# Step-sch.net
KiCad netlist of a schematic drawn in EAGLE
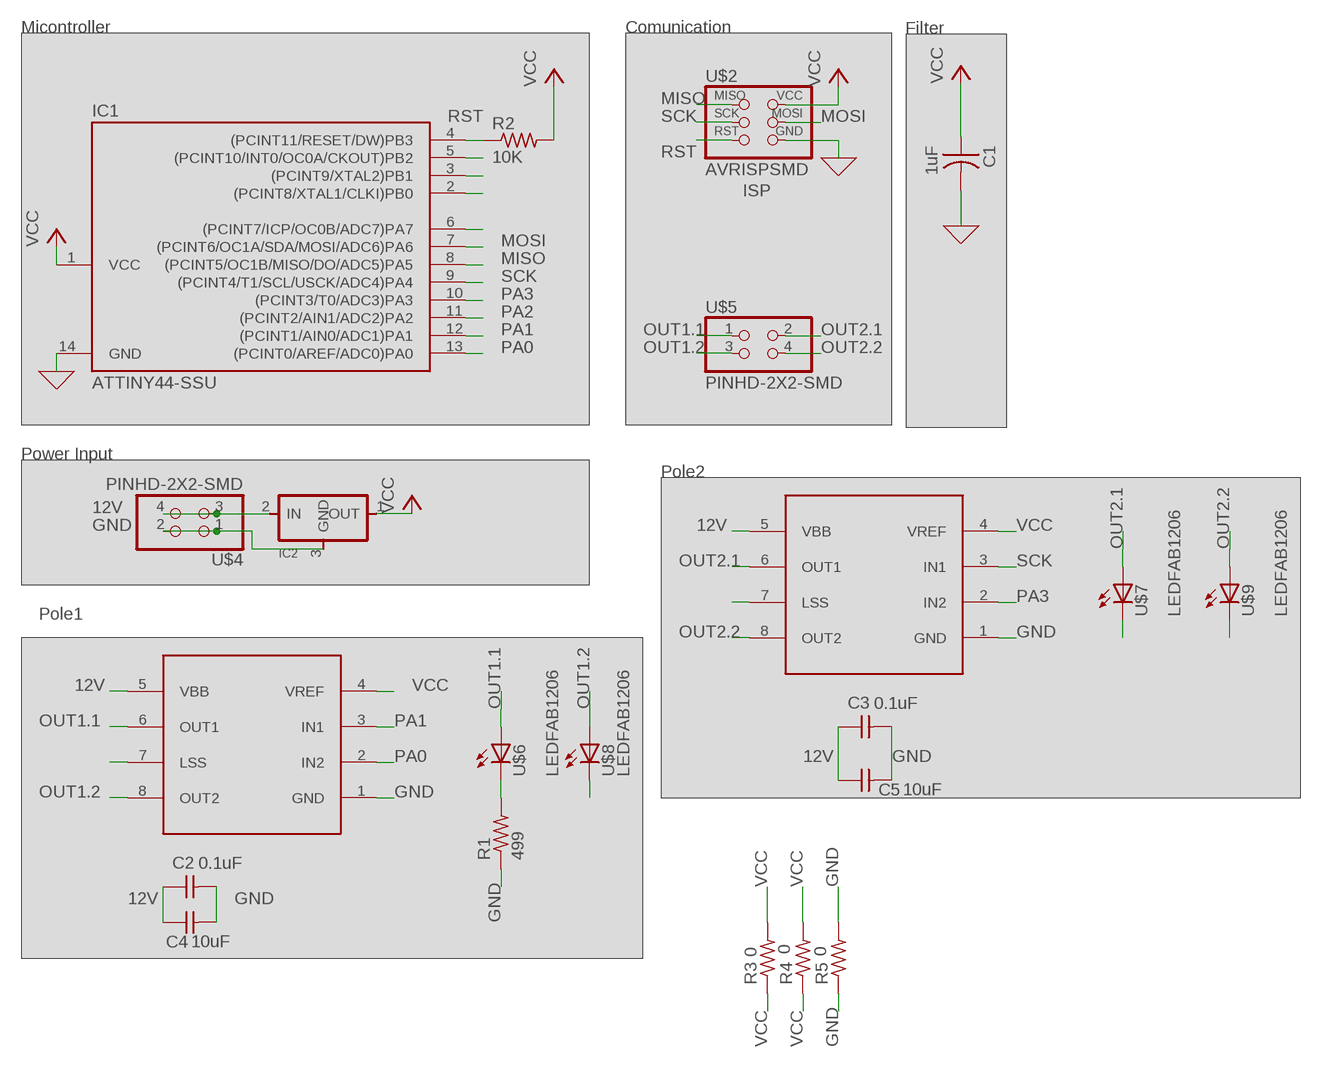
[diagram p0: schematic, sheet 1]

(export (version "E")
  (design (tool "Eeschema 10.0.6"))
  (components
    (comp (ref "C1")
      (value "1uF")
      (footprint "eagle-import:C1206FAB")
      (libsource (lib "eagle-import") (part "CAP-US1206FAB"))
    )
    (comp (ref "C2")
      (value "0.1uF")
      (footprint "eagle-import:C1206FAB")
      (libsource (lib "eagle-import") (part "CAP-UNPOLARIZEDFAB"))
    )
    (comp (ref "C3")
      (value "0.1uF")
      (footprint "eagle-import:C1206FAB")
      (libsource (lib "eagle-import") (part "CAP-UNPOLARIZEDFAB"))
    )
    (comp (ref "C4")
      (value "10uF")
      (footprint "eagle-import:C1206FAB")
      (libsource (lib "eagle-import") (part "CAP-UNPOLARIZEDFAB"))
    )
    (comp (ref "C5")
      (value "10uF")
      (footprint "eagle-import:C1206FAB")
      (libsource (lib "eagle-import") (part "CAP-UNPOLARIZEDFAB"))
    )
    (comp (ref "IC1")
      (value "ATTINY44-SSU")
      (footprint "eagle-import:SOIC14")
      (libsource (lib "eagle-import") (part "ATTINY44-SSU"))
    )
    (comp (ref "IC2")
      (value "REGULATORSOT23")
      (footprint "eagle-import:SOT23")
      (libsource (lib "eagle-import") (part "REGULATORSOT23"))
    )
    (comp (ref "R1")
      (value "499")
      (footprint "eagle-import:R1206FAB")
      (libsource (lib "eagle-import") (part "RES-US1206FAB"))
    )
    (comp (ref "R2")
      (value "10K")
      (footprint "eagle-import:R1206FAB")
      (libsource (lib "eagle-import") (part "RES-US1206FAB"))
    )
    (comp (ref "R3")
      (value "0")
      (footprint "eagle-import:R1206FAB")
      (libsource (lib "eagle-import") (part "RES-US1206FAB"))
    )
    (comp (ref "R4")
      (value "0")
      (footprint "eagle-import:R1206FAB")
      (libsource (lib "eagle-import") (part "RES-US1206FAB"))
    )
    (comp (ref "R5")
      (value "0")
      (footprint "eagle-import:R1206FAB")
      (libsource (lib "eagle-import") (part "RES-US1206FAB"))
    )
    (comp (ref "U$1")
      (value "A4953-H-BRIDGE-MOTOR-DRIVER")
      (footprint "eagle-import:SOIC8")
      (libsource (lib "eagle-import") (part "A4953-H-BRIDGE-MOTOR-DRIVER"))
    )
    (comp (ref "U$2")
      (value "AVRISPSMD")
      (footprint "eagle-import:2X03SMD")
      (libsource (lib "eagle-import") (part "AVRISPSMD"))
    )
    (comp (ref "U$3")
      (value "A4953-H-BRIDGE-MOTOR-DRIVER")
      (footprint "eagle-import:SOIC8")
      (libsource (lib "eagle-import") (part "A4953-H-BRIDGE-MOTOR-DRIVER"))
    )
    (comp (ref "U$4")
      (value "PINHD-2X2-SMD")
      (footprint "eagle-import:2X02SMD")
      (libsource (lib "eagle-import") (part "PINHD-2X2-SMD"))
    )
    (comp (ref "U$5")
      (value "PINHD-2X2-SMD")
      (footprint "eagle-import:2X02SMD")
      (libsource (lib "eagle-import") (part "PINHD-2X2-SMD"))
    )
    (comp (ref "U$6")
      (value "LEDFAB1206")
      (footprint "eagle-import:LED1206FAB")
      (libsource (lib "eagle-import") (part "LEDFAB1206"))
    )
    (comp (ref "U$7")
      (value "LEDFAB1206")
      (footprint "eagle-import:LED1206FAB")
      (libsource (lib "eagle-import") (part "LEDFAB1206"))
    )
    (comp (ref "U$8")
      (value "LEDFAB1206")
      (footprint "eagle-import:LED1206FAB")
      (libsource (lib "eagle-import") (part "LEDFAB1206"))
    )
    (comp (ref "U$9")
      (value "LEDFAB1206")
      (footprint "eagle-import:LED1206FAB")
      (libsource (lib "eagle-import") (part "LEDFAB1206"))
    )
  )
  (nets
    (net (code "1") (name "/12V") (class "Default")
      (node (ref "C2") (pin "1") (pinfunction "1_1") (pintype "passive"))
      (node (ref "C3") (pin "1") (pinfunction "1_1") (pintype "passive"))
      (node (ref "C4") (pin "1") (pinfunction "1_1") (pintype "passive"))
      (node (ref "C5") (pin "1") (pinfunction "1_1") (pintype "passive"))
      (node (ref "IC2") (pin "2") (pinfunction "IN_2") (pintype "bidirectional"))
      (node (ref "U$1") (pin "5") (pinfunction "VBB_5") (pintype "bidirectional"))
      (node (ref "U$3") (pin "5") (pinfunction "VBB_5") (pintype "bidirectional"))
      (node (ref "U$4") (pin "3") (pinfunction "3_3") (pintype "passive"))
      (node (ref "U$4") (pin "4") (pinfunction "4_4") (pintype "passive"))
    )
    (net (code "2") (name "/MISO") (class "Default")
      (node (ref "IC1") (pin "6") (pinfunction "(PCINT7/ICP/OC0B/ADC7)PA7_6") (pintype "bidirectional"))
      (node (ref "IC1") (pin "8") (pinfunction "(PCINT5/OC1B/MISO/DO/ADC5)PA5_8") (pintype "bidirectional"))
      (node (ref "U$2") (pin "1") (pinfunction "MISO_1") (pintype "passive"))
    )
    (net (code "3") (name "/MOSI") (class "Default")
      (node (ref "IC1") (pin "7") (pinfunction "(PCINT6/OC1A/SDA/MOSI/ADC6)PA6_7") (pintype "bidirectional"))
      (node (ref "U$2") (pin "4") (pinfunction "MOSI_4") (pintype "passive"))
    )
    (net (code "4") (name "/OUT1.1") (class "Default")
      (node (ref "U$1") (pin "6") (pinfunction "OUT1_6") (pintype "bidirectional"))
      (node (ref "U$5") (pin "1") (pinfunction "1_1") (pintype "passive"))
      (node (ref "U$6") (pin "1") (pinfunction "A_1") (pintype "passive"))
    )
    (net (code "5") (name "/OUT1.2") (class "Default")
      (node (ref "U$1") (pin "8") (pinfunction "OUT2_8") (pintype "bidirectional"))
      (node (ref "U$5") (pin "3") (pinfunction "3_3") (pintype "passive"))
      (node (ref "U$8") (pin "1") (pinfunction "A_1") (pintype "passive"))
    )
    (net (code "6") (name "/OUT2.1") (class "Default")
      (node (ref "U$3") (pin "6") (pinfunction "OUT1_6") (pintype "bidirectional"))
      (node (ref "U$5") (pin "2") (pinfunction "2_2") (pintype "passive"))
      (node (ref "U$7") (pin "1") (pinfunction "A_1") (pintype "passive"))
    )
    (net (code "7") (name "/OUT2.2") (class "Default")
      (node (ref "U$3") (pin "8") (pinfunction "OUT2_8") (pintype "bidirectional"))
      (node (ref "U$5") (pin "4") (pinfunction "4_4") (pintype "passive"))
      (node (ref "U$9") (pin "1") (pinfunction "A_1") (pintype "passive"))
    )
    (net (code "8") (name "/PA0") (class "Default")
      (node (ref "IC1") (pin "13") (pinfunction "(PCINT0/AREF/ADC0)PA0_13") (pintype "bidirectional"))
      (node (ref "U$1") (pin "2") (pinfunction "IN2_2") (pintype "bidirectional"))
    )
    (net (code "9") (name "/PA1") (class "Default")
      (node (ref "IC1") (pin "12") (pinfunction "(PCINT1/AIN0/ADC1)PA1_12") (pintype "bidirectional"))
      (node (ref "U$1") (pin "3") (pinfunction "IN1_3") (pintype "bidirectional"))
    )
    (net (code "10") (name "/PA2") (class "Default")
      (node (ref "IC1") (pin "11") (pinfunction "(PCINT2/AIN1/ADC2)PA2_11") (pintype "bidirectional"))
    )
    (net (code "11") (name "/PA3") (class "Default")
      (node (ref "IC1") (pin "10") (pinfunction "(PCINT3/T0/ADC3)PA3_10") (pintype "bidirectional"))
      (node (ref "U$3") (pin "2") (pinfunction "IN2_2") (pintype "bidirectional"))
    )
    (net (code "12") (name "/RES") (class "Default")
      (node (ref "R1") (pin "2") (pinfunction "2_2") (pintype "passive"))
      (node (ref "U$6") (pin "2") (pinfunction "C_2") (pintype "passive"))
      (node (ref "U$7") (pin "2") (pinfunction "C_2") (pintype "passive"))
      (node (ref "U$8") (pin "2") (pinfunction "C_2") (pintype "passive"))
      (node (ref "U$9") (pin "2") (pinfunction "C_2") (pintype "passive"))
    )
    (net (code "13") (name "/RST") (class "Default")
      (node (ref "IC1") (pin "4") (pinfunction "(PCINT11/RESET/DW)PB3_4") (pintype "bidirectional"))
      (node (ref "R2") (pin "1") (pinfunction "1_1") (pintype "passive"))
      (node (ref "U$2") (pin "5") (pinfunction "RST_5") (pintype "passive"))
    )
    (net (code "14") (name "/SCK") (class "Default")
      (node (ref "IC1") (pin "9") (pinfunction "(PCINT4/T1/SCL/USCK/ADC4)PA4_9") (pintype "bidirectional"))
      (node (ref "U$2") (pin "3") (pinfunction "SCK_3") (pintype "passive"))
      (node (ref "U$3") (pin "3") (pinfunction "IN1_3") (pintype "bidirectional"))
    )
    (net (code "15") (name "GND") (class "Default")
      (node (ref "C1") (pin "2") (pinfunction "2_2") (pintype "passive"))
      (node (ref "C2") (pin "2") (pinfunction "2_2") (pintype "passive"))
      (node (ref "C3") (pin "2") (pinfunction "2_2") (pintype "passive"))
      (node (ref "C4") (pin "2") (pinfunction "2_2") (pintype "passive"))
      (node (ref "C5") (pin "2") (pinfunction "2_2") (pintype "passive"))
      (node (ref "IC1") (pin "14") (pinfunction "GND_14") (pintype "power_in"))
      (node (ref "IC2") (pin "3") (pinfunction "GND_3") (pintype "bidirectional"))
      (node (ref "R1") (pin "1") (pinfunction "1_1") (pintype "passive"))
      (node (ref "R5") (pin "1") (pinfunction "1_1") (pintype "passive"))
      (node (ref "R5") (pin "2") (pinfunction "2_2") (pintype "passive"))
      (node (ref "U$1") (pin "1") (pinfunction "GND_1") (pintype "bidirectional"))
      (node (ref "U$2") (pin "6") (pinfunction "GND_6") (pintype "passive"))
      (node (ref "U$3") (pin "1") (pinfunction "GND_1") (pintype "bidirectional"))
      (node (ref "U$4") (pin "1") (pinfunction "1_1") (pintype "passive"))
      (node (ref "U$4") (pin "2") (pinfunction "2_2") (pintype "passive"))
    )
    (net (code "16") (name "VCC") (class "Default")
      (node (ref "C1") (pin "1") (pinfunction "1_1") (pintype "passive"))
      (node (ref "IC1") (pin "1") (pinfunction "VCC_1") (pintype "power_in"))
      (node (ref "IC2") (pin "1") (pinfunction "OUT_1") (pintype "bidirectional"))
      (node (ref "R2") (pin "2") (pinfunction "2_2") (pintype "passive"))
      (node (ref "R3") (pin "1") (pinfunction "1_1") (pintype "passive"))
      (node (ref "R3") (pin "2") (pinfunction "2_2") (pintype "passive"))
      (node (ref "R4") (pin "1") (pinfunction "1_1") (pintype "passive"))
      (node (ref "R4") (pin "2") (pinfunction "2_2") (pintype "passive"))
      (node (ref "U$1") (pin "4") (pinfunction "VREF_4") (pintype "bidirectional"))
      (node (ref "U$2") (pin "2") (pinfunction "VCC_2") (pintype "passive"))
      (node (ref "U$3") (pin "4") (pinfunction "VREF_4") (pintype "bidirectional"))
    )
    (net (code "17") (name "unconnected-(IC1-(PCINT8{slash}XTAL1{slash}CLKI)PB0-Pad2)") (class "Default")
      (node (ref "IC1") (pin "2") (pinfunction "(PCINT8/XTAL1/CLKI)PB0_2") (pintype "bidirectional"))
    )
    (net (code "18") (name "unconnected-(IC1-(PCINT9{slash}XTAL2)PB1-Pad3)") (class "Default")
      (node (ref "IC1") (pin "3") (pinfunction "(PCINT9/XTAL2)PB1_3") (pintype "bidirectional"))
    )
    (net (code "19") (name "unconnected-(IC1-(PCINT10{slash}INT0{slash}OC0A{slash}CKOUT)PB2-Pad5)") (class "Default")
      (node (ref "IC1") (pin "5") (pinfunction "(PCINT10/INT0/OC0A/CKOUT)PB2_5") (pintype "bidirectional"))
    )
    (net (code "20") (name "unconnected-(U$1-LSS-Pad7)") (class "Default")
      (node (ref "U$1") (pin "7") (pinfunction "LSS_7") (pintype "bidirectional"))
    )
    (net (code "21") (name "unconnected-(U$3-LSS-Pad7)") (class "Default")
      (node (ref "U$3") (pin "7") (pinfunction "LSS_7") (pintype "bidirectional"))
    )
  )
)
